# connector.net
KiCad netlist of a schematic drawn in Altium Designer
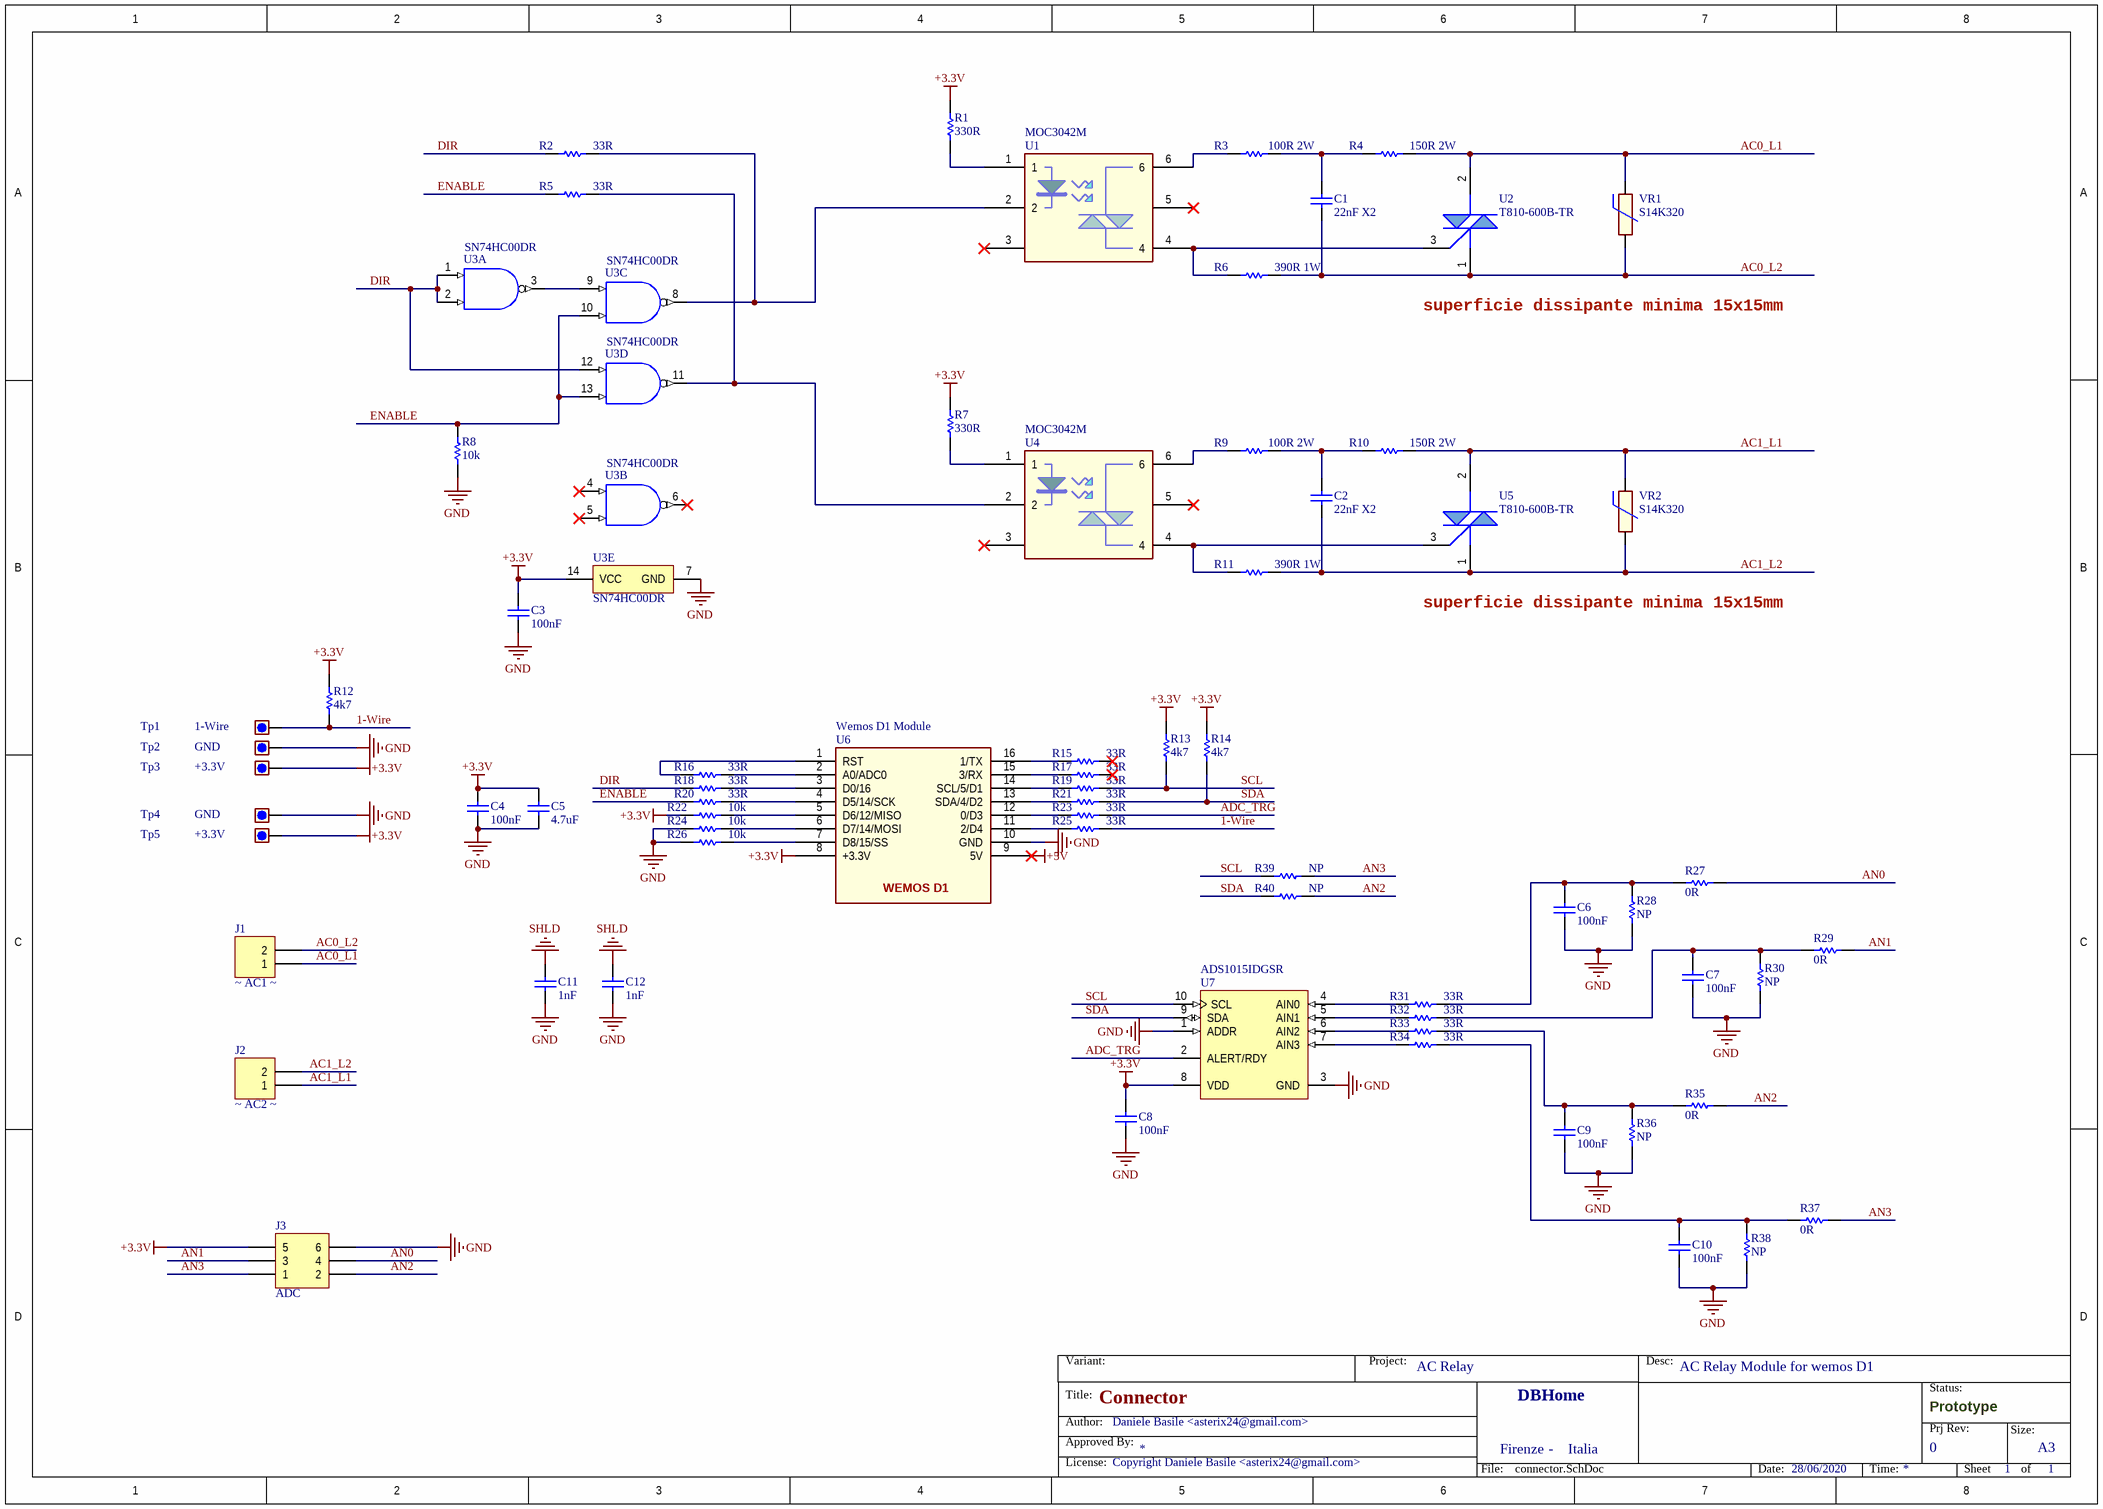
[diagram p0: connector.SchDoc]

(export (version "E")
  (design (tool "Eeschema 10.0.6"))
  (components
    (comp (ref "C1")
      (value "22nF X2")
      (footprint "RADIAL-10MM")
      (description "Capacitor X2 275V")
      (libsource (lib "develer_library") (part "Cap"))
    )
    (comp (ref "C2")
      (value "22nF X2")
      (footprint "RADIAL-10MM")
      (description "Capacitor X2 275V")
      (libsource (lib "develer_library") (part "Cap"))
    )
    (comp (ref "C3")
      (value "100nF")
      (footprint "0402_[1005]")
      (description "Capacitor")
      (libsource (lib "develer_library") (part "Cap"))
    )
    (comp (ref "C4")
      (value "100nF")
      (footprint "0402_[1005]")
      (description "Capacitor")
      (libsource (lib "develer_library") (part "Cap"))
    )
    (comp (ref "C5")
      (value "4.7uF")
      (footprint "0805_[2012]")
      (description "Capacitor")
      (libsource (lib "develer_library") (part "Cap"))
    )
    (comp (ref "C6")
      (value "100nF")
      (footprint "0402_[1005]")
      (description "Capacitor")
      (libsource (lib "develer_library") (part "Cap"))
    )
    (comp (ref "C7")
      (value "100nF")
      (footprint "0402_[1005]")
      (description "Capacitor")
      (libsource (lib "develer_library") (part "Cap"))
    )
    (comp (ref "C8")
      (value "100nF")
      (footprint "0402_[1005]")
      (description "Capacitor")
      (libsource (lib "develer_library") (part "Cap"))
    )
    (comp (ref "C9")
      (value "100nF")
      (footprint "0402_[1005]")
      (description "Capacitor")
      (libsource (lib "develer_library") (part "Cap"))
    )
    (comp (ref "C10")
      (value "100nF")
      (footprint "0402_[1005]")
      (description "Capacitor")
      (libsource (lib "develer_library") (part "Cap"))
    )
    (comp (ref "C11")
      (value "1nF")
      (footprint "0603_[1608]")
      (description "Capacitor")
      (libsource (lib "develer_library") (part "Cap"))
    )
    (comp (ref "C12")
      (value "1nF")
      (footprint "0603_[1608]")
      (description "Capacitor")
      (libsource (lib "develer_library") (part "Cap"))
    )
    (comp (ref "J1")
      (value "~ AC1 ~")
      (footprint "CON_WIRE_SCREW_2x1_5MM_THD")
      (description "Header, 2-Pin")
      (fields (field (name "PUBLISHER") "Altium Limited"))
      (libsource (lib "Miscellaneous Connectors") (part "Header 2"))
    )
    (comp (ref "J2")
      (value "~ AC2 ~")
      (footprint "CON_WIRE_SCREW_2x1_5MM_THD")
      (description "Header, 2-Pin")
      (fields (field (name "PUBLISHER") "Altium Limited"))
      (libsource (lib "Miscellaneous Connectors") (part "Header 2"))
    )
    (comp (ref "J3")
      (value "ADC")
      (footprint "CON_6P_WAGO_3.5mm")
      (description "Header, 3-Pin, Dual row")
      (fields (field (name "PUBLISHER") "Altium Limited"))
      (libsource (lib "Miscellaneous Connectors") (part "Header 3X2"))
    )
    (comp (ref "R1")
      (value "330R")
      (footprint "0402_[1005]")
      (description "Resistor")
      (fields (field (name "PUBLISHER") "Develer srl"))
      (libsource (lib "develer_library") (part "Res1"))
    )
    (comp (ref "R2")
      (value "33R")
      (footprint "0402_[1005]")
      (description "Resistor")
      (fields (field (name "PUBLISHER") "Develer srl"))
      (libsource (lib "develer_library") (part "Res1"))
    )
    (comp (ref "R3")
      (value "100R 2W")
      (footprint "2512_[6432]")
      (description "Resistor 300V (Walsin WF25P271)")
      (fields (field (name "PUBLISHER") "Develer srl"))
      (libsource (lib "develer_library") (part "Res1"))
    )
    (comp (ref "R4")
      (value "150R 2W")
      (footprint "2512_[6432]")
      (description "Resistor 2W 300V (Walsin WF25P471)")
      (fields (field (name "PUBLISHER") "Develer srl"))
      (libsource (lib "develer_library") (part "Res1"))
    )
    (comp (ref "R5")
      (value "33R")
      (footprint "0402_[1005]")
      (description "Resistor")
      (fields (field (name "PUBLISHER") "Develer srl"))
      (libsource (lib "develer_library") (part "Res1"))
    )
    (comp (ref "R6")
      (value "390R 1W")
      (footprint "2512_[6432]")
      (description "Resistor 1W 200V")
      (fields (field (name "PUBLISHER") "Develer srl"))
      (libsource (lib "develer_library") (part "Res1"))
    )
    (comp (ref "R7")
      (value "330R")
      (footprint "0402_[1005]")
      (description "Resistor")
      (fields (field (name "PUBLISHER") "Develer srl"))
      (libsource (lib "develer_library") (part "Res1"))
    )
    (comp (ref "R8")
      (value "10k")
      (footprint "0402_[1005]")
      (description "Resistor")
      (fields (field (name "PUBLISHER") "Develer srl"))
      (libsource (lib "develer_library") (part "Res1"))
    )
    (comp (ref "R9")
      (value "100R 2W")
      (footprint "2512_[6432]")
      (description "Resistor 300V (Walsin WF25P271)")
      (fields (field (name "PUBLISHER") "Develer srl"))
      (libsource (lib "develer_library") (part "Res1"))
    )
    (comp (ref "R10")
      (value "150R 2W")
      (footprint "2512_[6432]")
      (description "Resistor 2W 300V (Walsin WF25P471)")
      (fields (field (name "PUBLISHER") "Develer srl"))
      (libsource (lib "develer_library") (part "Res1"))
    )
    (comp (ref "R11")
      (value "390R 1W")
      (footprint "2512_[6432]")
      (description "Resistor 1W 200V")
      (fields (field (name "PUBLISHER") "Develer srl"))
      (libsource (lib "develer_library") (part "Res1"))
    )
    (comp (ref "R12")
      (value "4k7")
      (footprint "0402_[1005]")
      (description "Resistor")
      (fields (field (name "PUBLISHER") "Develer srl"))
      (libsource (lib "develer_library") (part "Res1"))
    )
    (comp (ref "R13")
      (value "4k7")
      (footprint "0402_[1005]")
      (description "Resistor")
      (fields (field (name "PUBLISHER") "Develer srl"))
      (libsource (lib "develer_library") (part "Res1"))
    )
    (comp (ref "R14")
      (value "4k7")
      (footprint "0402_[1005]")
      (description "Resistor")
      (fields (field (name "PUBLISHER") "Develer srl"))
      (libsource (lib "develer_library") (part "Res1"))
    )
    (comp (ref "R15")
      (value "33R")
      (footprint "0402_[1005]")
      (description "Resistor")
      (fields (field (name "PUBLISHER") "Develer srl"))
      (libsource (lib "develer_library") (part "Res1"))
    )
    (comp (ref "R16")
      (value "33R")
      (footprint "0402_[1005]")
      (description "Resistor")
      (fields (field (name "PUBLISHER") "Develer srl"))
      (libsource (lib "develer_library") (part "Res1"))
    )
    (comp (ref "R17")
      (value "33R")
      (footprint "0402_[1005]")
      (description "Resistor")
      (fields (field (name "PUBLISHER") "Develer srl"))
      (libsource (lib "develer_library") (part "Res1"))
    )
    (comp (ref "R18")
      (value "33R")
      (footprint "0402_[1005]")
      (description "Resistor")
      (fields (field (name "PUBLISHER") "Develer srl"))
      (libsource (lib "develer_library") (part "Res1"))
    )
    (comp (ref "R19")
      (value "33R")
      (footprint "0402_[1005]")
      (description "Resistor")
      (fields (field (name "PUBLISHER") "Develer srl"))
      (libsource (lib "develer_library") (part "Res1"))
    )
    (comp (ref "R20")
      (value "33R")
      (footprint "0402_[1005]")
      (description "Resistor")
      (fields (field (name "PUBLISHER") "Develer srl"))
      (libsource (lib "develer_library") (part "Res1"))
    )
    (comp (ref "R21")
      (value "33R")
      (footprint "0402_[1005]")
      (description "Resistor")
      (fields (field (name "PUBLISHER") "Develer srl"))
      (libsource (lib "develer_library") (part "Res1"))
    )
    (comp (ref "R22")
      (value "10k")
      (footprint "0402_[1005]")
      (description "Resistor")
      (fields (field (name "PUBLISHER") "Develer srl"))
      (libsource (lib "develer_library") (part "Res1"))
    )
    (comp (ref "R23")
      (value "33R")
      (footprint "0402_[1005]")
      (description "Resistor")
      (fields (field (name "PUBLISHER") "Develer srl"))
      (libsource (lib "develer_library") (part "Res1"))
    )
    (comp (ref "R24")
      (value "10k")
      (footprint "0402_[1005]")
      (description "Resistor")
      (fields (field (name "PUBLISHER") "Develer srl"))
      (libsource (lib "develer_library") (part "Res1"))
    )
    (comp (ref "R25")
      (value "33R")
      (footprint "0402_[1005]")
      (description "Resistor")
      (fields (field (name "PUBLISHER") "Develer srl"))
      (libsource (lib "develer_library") (part "Res1"))
    )
    (comp (ref "R26")
      (value "10k")
      (footprint "0402_[1005]")
      (description "Resistor")
      (fields (field (name "PUBLISHER") "Develer srl"))
      (libsource (lib "develer_library") (part "Res1"))
    )
    (comp (ref "R27")
      (value "0R")
      (footprint "0402_[1005]")
      (description "Resistor")
      (fields (field (name "PUBLISHER") "Develer srl"))
      (libsource (lib "develer_library") (part "Res1"))
    )
    (comp (ref "R28")
      (value "NP")
      (footprint "0402_[1005]")
      (description "Resistor")
      (fields (field (name "PUBLISHER") "Develer srl"))
      (libsource (lib "develer_library") (part "Res1"))
    )
    (comp (ref "R29")
      (value "0R")
      (footprint "0402_[1005]")
      (description "Resistor")
      (fields (field (name "PUBLISHER") "Develer srl"))
      (libsource (lib "develer_library") (part "Res1"))
    )
    (comp (ref "R30")
      (value "NP")
      (footprint "0402_[1005]")
      (description "Resistor")
      (fields (field (name "PUBLISHER") "Develer srl"))
      (libsource (lib "develer_library") (part "Res1"))
    )
    (comp (ref "R31")
      (value "33R")
      (footprint "0402_[1005]")
      (description "Resistor")
      (fields (field (name "PUBLISHER") "Develer srl"))
      (libsource (lib "develer_library") (part "Res1"))
    )
    (comp (ref "R32")
      (value "33R")
      (footprint "0402_[1005]")
      (description "Resistor")
      (fields (field (name "PUBLISHER") "Develer srl"))
      (libsource (lib "develer_library") (part "Res1"))
    )
    (comp (ref "R33")
      (value "33R")
      (footprint "0402_[1005]")
      (description "Resistor")
      (fields (field (name "PUBLISHER") "Develer srl"))
      (libsource (lib "develer_library") (part "Res1"))
    )
    (comp (ref "R34")
      (value "33R")
      (footprint "0402_[1005]")
      (description "Resistor")
      (fields (field (name "PUBLISHER") "Develer srl"))
      (libsource (lib "develer_library") (part "Res1"))
    )
    (comp (ref "R35")
      (value "0R")
      (footprint "0402_[1005]")
      (description "Resistor")
      (fields (field (name "PUBLISHER") "Develer srl"))
      (libsource (lib "develer_library") (part "Res1"))
    )
    (comp (ref "R36")
      (value "NP")
      (footprint "0402_[1005]")
      (description "Resistor")
      (fields (field (name "PUBLISHER") "Develer srl"))
      (libsource (lib "develer_library") (part "Res1"))
    )
    (comp (ref "R37")
      (value "0R")
      (footprint "0402_[1005]")
      (description "Resistor")
      (fields (field (name "PUBLISHER") "Develer srl"))
      (libsource (lib "develer_library") (part "Res1"))
    )
    (comp (ref "R38")
      (value "NP")
      (footprint "0402_[1005]")
      (description "Resistor")
      (fields (field (name "PUBLISHER") "Develer srl"))
      (libsource (lib "develer_library") (part "Res1"))
    )
    (comp (ref "R39")
      (value "NP")
      (footprint "0402_[1005]")
      (description "Resistor")
      (fields (field (name "PUBLISHER") "Develer srl"))
      (libsource (lib "develer_library") (part "Res1"))
    )
    (comp (ref "R40")
      (value "NP")
      (footprint "0402_[1005]")
      (description "Resistor")
      (fields (field (name "PUBLISHER") "Develer srl"))
      (libsource (lib "develer_library") (part "Res1"))
    )
    (comp (ref "Tp1")
      (value "1-Wire")
      (footprint "TEST_POINT_SMD_R5x3MM")
      (libsource (lib "develer_library") (part "Test_point"))
    )
    (comp (ref "Tp2")
      (value "GND")
      (footprint "TEST_POINT_SMD_R5x3MM")
      (libsource (lib "develer_library") (part "Test_point"))
    )
    (comp (ref "Tp3")
      (value "+3.3V")
      (footprint "TEST_POINT_SMD_R5x3MM")
      (libsource (lib "develer_library") (part "Test_point"))
    )
    (comp (ref "Tp4")
      (value "GND")
      (footprint "TEST_POINT_SMD_R5x3MM")
      (libsource (lib "develer_library") (part "Test_point"))
    )
    (comp (ref "Tp5")
      (value "+3.3V")
      (footprint "TEST_POINT_SMD_R5x3MM")
      (libsource (lib "develer_library") (part "Test_point"))
    )
    (comp (ref "U1")
      (value "MOC3042M")
      (footprint "SOIC6_OPTO")
      (description "Opto-triac")
      (fields (field (name "PUBLISHER") "Develer srl"))
      (libsource (lib "develer_library") (part "MOC302xS"))
    )
    (comp (ref "U2")
      (value "T810-600B-TR")
      (footprint "TO-252_D2PAK_LARGEPAD")
      (description "triac")
      (fields (field (name "PUBLISHER") "Develer srl"))
      (libsource (lib "develer_library") (part "triac"))
    )
    (comp (ref "U3")
      (value "SN74HC00DR")
      (footprint "SOIC14")
      (description "Quad 2-Input Positive-NAND Gates, D0014A, LARGE T&R")
      (fields
        (field (name "GENERIC PART NUMBER") "SN74HC00")
        (field (name "MANUFACTURER") "Texas Instruments")
      )
      (libsource (lib "develer_library") (part "TI-NAND-4-2IN-14_G"))
    )
    (comp (ref "U4")
      (value "MOC3042M")
      (footprint "SOIC6_OPTO")
      (description "Opto-triac")
      (fields (field (name "PUBLISHER") "Develer srl"))
      (libsource (lib "develer_library") (part "MOC302xS"))
    )
    (comp (ref "U5")
      (value "T810-600B-TR")
      (footprint "TO-252_D2PAK_LARGEPAD")
      (description "triac")
      (fields (field (name "PUBLISHER") "Develer srl"))
      (libsource (lib "develer_library") (part "triac"))
    )
    (comp (ref "U6")
      (value "Wemos D1 Module")
      (footprint "WEMOS_D1")
      (description "ComponetDescritions (altrenative1; alternativ2)")
      (fields (field (name "PUBLISHER") "Develer srl"))
      (libsource (lib "develer_library") (part "WEMOS D1"))
    )
    (comp (ref "U7")
      (value "ADS1015IDGSR")
      (footprint "MSOP50P490X110-10P")
      (fields (field (name "MANUFACTURER") "Texas Instruments"))
      (libsource (lib "develer_library") (part "TI-ADS1015_1115-10"))
    )
    (comp (ref "VR1")
      (value "S14K320")
      (footprint "VAR_DISC_7.5MM_THD")
      (description "ComponetDescritions (altrenative1; alternativ2)")
      (fields (field (name "PUBLISHER") "Develer srl"))
      (libsource (lib "develer_library") (part "VARISTOR"))
    )
    (comp (ref "VR2")
      (value "S14K320")
      (footprint "VAR_DISC_7.5MM_THD")
      (description "ComponetDescritions (altrenative1; alternativ2)")
      (fields (field (name "PUBLISHER") "Develer srl"))
      (libsource (lib "develer_library") (part "VARISTOR"))
    )
  )
  (nets
    (net (code "1") (name "+3.3V") (class "Default")
      (node (ref "C3") (pin "2") (pinfunction "2_2") (pintype "passive"))
      (node (ref "C4") (pin "2") (pinfunction "2_2") (pintype "passive"))
      (node (ref "C5") (pin "2") (pinfunction "2_2") (pintype "passive"))
      (node (ref "C8") (pin "2") (pinfunction "2_2") (pintype "passive"))
      (node (ref "J3") (pin "5") (pinfunction "5_5") (pintype "passive"))
      (node (ref "R1") (pin "2") (pinfunction "2_2") (pintype "passive"))
      (node (ref "R12") (pin "2") (pinfunction "2_2") (pintype "passive"))
      (node (ref "R13") (pin "2") (pinfunction "2_2") (pintype "passive"))
      (node (ref "R14") (pin "2") (pinfunction "2_2") (pintype "passive"))
      (node (ref "R22") (pin "2") (pinfunction "2_2") (pintype "passive"))
      (node (ref "R7") (pin "2") (pinfunction "2_2") (pintype "passive"))
      (node (ref "Tp3") (pin "1") (pinfunction "1_1") (pintype "passive"))
      (node (ref "Tp5") (pin "1") (pinfunction "1_1") (pintype "passive"))
      (node (ref "U3") (pin "14") (pinfunction "VCC_14") (pintype "power_in"))
      (node (ref "U6") (pin "8") (pinfunction "+3.3V_8") (pintype "passive"))
      (node (ref "U7") (pin "8") (pinfunction "VDD_8") (pintype "power_in"))
    )
    (net (code "2") (name "+5V") (class "Default")
      (node (ref "U6") (pin "9") (pinfunction "5V_9") (pintype "passive"))
    )
    (net (code "3") (name "/1-Wire") (class "Default")
      (node (ref "R12") (pin "1") (pinfunction "1_1") (pintype "passive"))
      (node (ref "R25") (pin "1") (pinfunction "1_1") (pintype "passive"))
      (node (ref "Tp1") (pin "1") (pinfunction "1_1") (pintype "passive"))
    )
    (net (code "4") (name "/AC0_L1") (class "Default")
      (node (ref "J1") (pin "1") (pinfunction "1_1") (pintype "passive"))
      (node (ref "R4") (pin "1") (pinfunction "1_1") (pintype "passive"))
      (node (ref "U2") (pin "2") (pinfunction "2_2") (pintype "passive"))
      (node (ref "VR1") (pin "2") (pinfunction "2_2") (pintype "passive"))
    )
    (net (code "5") (name "/AC0_L2") (class "Default")
      (node (ref "C1") (pin "1") (pinfunction "1_1") (pintype "passive"))
      (node (ref "J1") (pin "2") (pinfunction "2_2") (pintype "passive"))
      (node (ref "R6") (pin "1") (pinfunction "1_1") (pintype "passive"))
      (node (ref "U2") (pin "1") (pinfunction "1_1") (pintype "passive"))
      (node (ref "VR1") (pin "1") (pinfunction "1_1") (pintype "passive"))
    )
    (net (code "6") (name "/AC1_L1") (class "Default")
      (node (ref "J2") (pin "1") (pinfunction "1_1") (pintype "passive"))
      (node (ref "R10") (pin "1") (pinfunction "1_1") (pintype "passive"))
      (node (ref "U5") (pin "2") (pinfunction "2_2") (pintype "passive"))
      (node (ref "VR2") (pin "2") (pinfunction "2_2") (pintype "passive"))
    )
    (net (code "7") (name "/AC1_L2") (class "Default")
      (node (ref "C2") (pin "1") (pinfunction "1_1") (pintype "passive"))
      (node (ref "J2") (pin "2") (pinfunction "2_2") (pintype "passive"))
      (node (ref "R11") (pin "1") (pinfunction "1_1") (pintype "passive"))
      (node (ref "U5") (pin "1") (pinfunction "1_1") (pintype "passive"))
      (node (ref "VR2") (pin "1") (pinfunction "1_1") (pintype "passive"))
    )
    (net (code "8") (name "/ADC_TRG") (class "Default")
      (node (ref "R23") (pin "1") (pinfunction "1_1") (pintype "passive"))
      (node (ref "U7") (pin "2") (pinfunction "ALERT/RDY_2") (pintype "open_collector"))
    )
    (net (code "9") (name "/AN0") (class "Default")
      (node (ref "J3") (pin "4") (pinfunction "4_4") (pintype "passive"))
      (node (ref "R27") (pin "2") (pinfunction "2_2") (pintype "passive"))
    )
    (net (code "10") (name "/AN1") (class "Default")
      (node (ref "J3") (pin "3") (pinfunction "3_3") (pintype "passive"))
      (node (ref "R29") (pin "2") (pinfunction "2_2") (pintype "passive"))
    )
    (net (code "11") (name "/AN2") (class "Default")
      (node (ref "J3") (pin "2") (pinfunction "2_2") (pintype "passive"))
      (node (ref "R35") (pin "2") (pinfunction "2_2") (pintype "passive"))
      (node (ref "R40") (pin "2") (pinfunction "2_2") (pintype "passive"))
    )
    (net (code "12") (name "/AN3") (class "Default")
      (node (ref "J3") (pin "1") (pinfunction "1_1") (pintype "passive"))
      (node (ref "R37") (pin "2") (pinfunction "2_2") (pintype "passive"))
      (node (ref "R39") (pin "2") (pinfunction "2_2") (pintype "passive"))
    )
    (net (code "13") (name "/DIR") (class "Default")
      (node (ref "R18") (pin "2") (pinfunction "2_2") (pintype "passive"))
      (node (ref "R2") (pin "2") (pinfunction "2_2") (pintype "passive"))
      (node (ref "U3") (pin "1") (pinfunction "1A_1") (pintype "input"))
      (node (ref "U3") (pin "12") (pinfunction "4A_12") (pintype "input"))
      (node (ref "U3") (pin "2") (pinfunction "1B_2") (pintype "input"))
    )
    (net (code "14") (name "/ENABLE") (class "Default")
      (node (ref "R20") (pin "2") (pinfunction "2_2") (pintype "passive"))
      (node (ref "R5") (pin "2") (pinfunction "2_2") (pintype "passive"))
      (node (ref "R8") (pin "1") (pinfunction "1_1") (pintype "passive"))
      (node (ref "U3") (pin "10") (pinfunction "3B_10") (pintype "input"))
      (node (ref "U3") (pin "13") (pinfunction "4B_13") (pintype "input"))
    )
    (net (code "15") (name "/SCL") (class "Default")
      (node (ref "R13") (pin "1") (pinfunction "1_1") (pintype "passive"))
      (node (ref "R19") (pin "1") (pinfunction "1_1") (pintype "passive"))
      (node (ref "R39") (pin "1") (pinfunction "1_1") (pintype "passive"))
      (node (ref "U7") (pin "10") (pinfunction "SCL_10") (pintype "input"))
    )
    (net (code "16") (name "/SDA") (class "Default")
      (node (ref "R14") (pin "1") (pinfunction "1_1") (pintype "passive"))
      (node (ref "R21") (pin "1") (pinfunction "1_1") (pintype "passive"))
      (node (ref "R40") (pin "1") (pinfunction "1_1") (pintype "passive"))
      (node (ref "U7") (pin "9") (pinfunction "SDA_9") (pintype "bidirectional"))
    )
    (net (code "17") (name "GND") (class "Default")
      (node (ref "C10") (pin "1") (pinfunction "1_1") (pintype "passive"))
      (node (ref "C11") (pin "1") (pinfunction "1_1") (pintype "passive"))
      (node (ref "C12") (pin "1") (pinfunction "1_1") (pintype "passive"))
      (node (ref "C3") (pin "1") (pinfunction "1_1") (pintype "passive"))
      (node (ref "C4") (pin "1") (pinfunction "1_1") (pintype "passive"))
      (node (ref "C5") (pin "1") (pinfunction "1_1") (pintype "passive"))
      (node (ref "C6") (pin "1") (pinfunction "1_1") (pintype "passive"))
      (node (ref "C7") (pin "1") (pinfunction "1_1") (pintype "passive"))
      (node (ref "C8") (pin "1") (pinfunction "1_1") (pintype "passive"))
      (node (ref "C9") (pin "1") (pinfunction "1_1") (pintype "passive"))
      (node (ref "J3") (pin "6") (pinfunction "6_6") (pintype "passive"))
      (node (ref "R24") (pin "2") (pinfunction "2_2") (pintype "passive"))
      (node (ref "R26") (pin "2") (pinfunction "2_2") (pintype "passive"))
      (node (ref "R28") (pin "2") (pinfunction "2_2") (pintype "passive"))
      (node (ref "R30") (pin "2") (pinfunction "2_2") (pintype "passive"))
      (node (ref "R36") (pin "2") (pinfunction "2_2") (pintype "passive"))
      (node (ref "R38") (pin "2") (pinfunction "2_2") (pintype "passive"))
      (node (ref "R8") (pin "2") (pinfunction "2_2") (pintype "passive"))
      (node (ref "Tp2") (pin "1") (pinfunction "1_1") (pintype "passive"))
      (node (ref "Tp4") (pin "1") (pinfunction "1_1") (pintype "passive"))
      (node (ref "U3") (pin "7") (pinfunction "GND_7") (pintype "power_in"))
      (node (ref "U6") (pin "10") (pinfunction "GND_10") (pintype "passive"))
      (node (ref "U7") (pin "1") (pinfunction "ADDR_1") (pintype "input"))
      (node (ref "U7") (pin "3") (pinfunction "GND_3") (pintype "power_in"))
    )
    (net (code "18") (name "Net-(C1-Pad2)") (class "Default")
      (node (ref "C1") (pin "2") (pinfunction "2_2") (pintype "passive"))
      (node (ref "R3") (pin "1") (pinfunction "1_1") (pintype "passive"))
      (node (ref "R4") (pin "2") (pinfunction "2_2") (pintype "passive"))
    )
    (net (code "19") (name "Net-(C2-Pad2)") (class "Default")
      (node (ref "C2") (pin "2") (pinfunction "2_2") (pintype "passive"))
      (node (ref "R10") (pin "2") (pinfunction "2_2") (pintype "passive"))
      (node (ref "R9") (pin "1") (pinfunction "1_1") (pintype "passive"))
    )
    (net (code "20") (name "Net-(C6-Pad2)") (class "Default")
      (node (ref "C6") (pin "2") (pinfunction "2_2") (pintype "passive"))
      (node (ref "R27") (pin "1") (pinfunction "1_1") (pintype "passive"))
      (node (ref "R28") (pin "1") (pinfunction "1_1") (pintype "passive"))
      (node (ref "R31") (pin "1") (pinfunction "1_1") (pintype "passive"))
    )
    (net (code "21") (name "Net-(C7-Pad2)") (class "Default")
      (node (ref "C7") (pin "2") (pinfunction "2_2") (pintype "passive"))
      (node (ref "R29") (pin "1") (pinfunction "1_1") (pintype "passive"))
      (node (ref "R30") (pin "1") (pinfunction "1_1") (pintype "passive"))
      (node (ref "R32") (pin "1") (pinfunction "1_1") (pintype "passive"))
    )
    (net (code "22") (name "Net-(C9-Pad2)") (class "Default")
      (node (ref "C9") (pin "2") (pinfunction "2_2") (pintype "passive"))
      (node (ref "R33") (pin "1") (pinfunction "1_1") (pintype "passive"))
      (node (ref "R35") (pin "1") (pinfunction "1_1") (pintype "passive"))
      (node (ref "R36") (pin "1") (pinfunction "1_1") (pintype "passive"))
    )
    (net (code "23") (name "Net-(C10-Pad2)") (class "Default")
      (node (ref "C10") (pin "2") (pinfunction "2_2") (pintype "passive"))
      (node (ref "R34") (pin "1") (pinfunction "1_1") (pintype "passive"))
      (node (ref "R37") (pin "1") (pinfunction "1_1") (pintype "passive"))
      (node (ref "R38") (pin "1") (pinfunction "1_1") (pintype "passive"))
    )
    (net (code "24") (name "Net-(R1-Pad1)") (class "Default")
      (node (ref "R1") (pin "1") (pinfunction "1_1") (pintype "passive"))
      (node (ref "U1") (pin "1") (pinfunction "1_1") (pintype "passive"))
    )
    (net (code "25") (name "Net-(R3-Pad2)") (class "Default")
      (node (ref "R3") (pin "2") (pinfunction "2_2") (pintype "passive"))
      (node (ref "U1") (pin "6") (pinfunction "6_6") (pintype "passive"))
    )
    (net (code "26") (name "Net-(R6-Pad2)") (class "Default")
      (node (ref "R6") (pin "2") (pinfunction "2_2") (pintype "passive"))
      (node (ref "U1") (pin "4") (pinfunction "4_4") (pintype "passive"))
      (node (ref "U2") (pin "3") (pinfunction "3_3") (pintype "passive"))
    )
    (net (code "27") (name "Net-(R7-Pad1)") (class "Default")
      (node (ref "R7") (pin "1") (pinfunction "1_1") (pintype "passive"))
      (node (ref "U4") (pin "1") (pinfunction "1_1") (pintype "passive"))
    )
    (net (code "28") (name "Net-(R9-Pad2)") (class "Default")
      (node (ref "R9") (pin "2") (pinfunction "2_2") (pintype "passive"))
      (node (ref "U4") (pin "6") (pinfunction "6_6") (pintype "passive"))
    )
    (net (code "29") (name "Net-(R11-Pad2)") (class "Default")
      (node (ref "R11") (pin "2") (pinfunction "2_2") (pintype "passive"))
      (node (ref "U4") (pin "4") (pinfunction "4_4") (pintype "passive"))
      (node (ref "U5") (pin "3") (pinfunction "3_3") (pintype "passive"))
    )
    (net (code "30") (name "Net-(U3A-1Y)") (class "Default")
      (node (ref "U3") (pin "3") (pinfunction "1Y_3") (pintype "output"))
      (node (ref "U3") (pin "9") (pinfunction "3A_9") (pintype "input"))
    )
    (net (code "31") (name "Net-(U3C-3Y)") (class "Default")
      (node (ref "R2") (pin "1") (pinfunction "1_1") (pintype "passive"))
      (node (ref "U1") (pin "2") (pinfunction "2_2") (pintype "passive"))
      (node (ref "U3") (pin "8") (pinfunction "3Y_8") (pintype "output"))
    )
    (net (code "32") (name "Net-(U3D-4Y)") (class "Default")
      (node (ref "R5") (pin "1") (pinfunction "1_1") (pintype "passive"))
      (node (ref "U3") (pin "11") (pinfunction "4Y_11") (pintype "output"))
      (node (ref "U4") (pin "2") (pinfunction "2_2") (pintype "passive"))
    )
    (net (code "33") (name "Net-(U6-0{slash}D3)") (class "Default")
      (node (ref "R23") (pin "2") (pinfunction "2_2") (pintype "passive"))
      (node (ref "U6") (pin "12") (pinfunction "0/D3_12") (pintype "passive"))
    )
    (net (code "34") (name "Net-(U6-1{slash}TX)") (class "Default")
      (node (ref "R15") (pin "2") (pinfunction "2_2") (pintype "passive"))
      (node (ref "U6") (pin "16") (pinfunction "1/TX_16") (pintype "passive"))
    )
    (net (code "35") (name "Net-(U6-2{slash}D4)") (class "Default")
      (node (ref "R25") (pin "2") (pinfunction "2_2") (pintype "passive"))
      (node (ref "U6") (pin "11") (pinfunction "2/D4_11") (pintype "passive"))
    )
    (net (code "36") (name "Net-(U6-3{slash}RX)") (class "Default")
      (node (ref "R17") (pin "2") (pinfunction "2_2") (pintype "passive"))
      (node (ref "U6") (pin "15") (pinfunction "3/RX_15") (pintype "passive"))
    )
    (net (code "37") (name "Net-(U6-A0{slash}ADC0)") (class "Default")
      (node (ref "R16") (pin "1") (pinfunction "1_1") (pintype "passive"))
      (node (ref "U6") (pin "2") (pinfunction "A0/ADC0_2") (pintype "passive"))
    )
    (net (code "38") (name "Net-(U6-D0{slash}16)") (class "Default")
      (node (ref "R18") (pin "1") (pinfunction "1_1") (pintype "passive"))
      (node (ref "U6") (pin "3") (pinfunction "D0/16_3") (pintype "passive"))
    )
    (net (code "39") (name "Net-(U6-D5{slash}14{slash}SCK)") (class "Default")
      (node (ref "R20") (pin "1") (pinfunction "1_1") (pintype "passive"))
      (node (ref "U6") (pin "4") (pinfunction "D5/14/SCK_4") (pintype "passive"))
    )
    (net (code "40") (name "Net-(U6-D6{slash}12{slash}MISO)") (class "Default")
      (node (ref "R22") (pin "1") (pinfunction "1_1") (pintype "passive"))
      (node (ref "U6") (pin "5") (pinfunction "D6/12/MISO_5") (pintype "passive"))
    )
    (net (code "41") (name "Net-(U6-D7{slash}14{slash}MOSI)") (class "Default")
      (node (ref "R24") (pin "1") (pinfunction "1_1") (pintype "passive"))
      (node (ref "U6") (pin "6") (pinfunction "D7/14/MOSI_6") (pintype "passive"))
    )
    (net (code "42") (name "Net-(U6-D8{slash}15{slash}SS)") (class "Default")
      (node (ref "R26") (pin "1") (pinfunction "1_1") (pintype "passive"))
      (node (ref "U6") (pin "7") (pinfunction "D8/15/SS_7") (pintype "passive"))
    )
    (net (code "43") (name "Net-(U6-RST)") (class "Default")
      (node (ref "R16") (pin "2") (pinfunction "2_2") (pintype "passive"))
      (node (ref "U6") (pin "1") (pinfunction "RST_1") (pintype "passive"))
    )
    (net (code "44") (name "Net-(U6-SCL{slash}5{slash}D1)") (class "Default")
      (node (ref "R19") (pin "2") (pinfunction "2_2") (pintype "passive"))
      (node (ref "U6") (pin "14") (pinfunction "SCL/5/D1_14") (pintype "passive"))
    )
    (net (code "45") (name "Net-(U6-SDA{slash}4{slash}D2)") (class "Default")
      (node (ref "R21") (pin "2") (pinfunction "2_2") (pintype "passive"))
      (node (ref "U6") (pin "13") (pinfunction "SDA/4/D2_13") (pintype "passive"))
    )
    (net (code "46") (name "Net-(U7-AIN0)") (class "Default")
      (node (ref "R31") (pin "2") (pinfunction "2_2") (pintype "passive"))
      (node (ref "U7") (pin "4") (pinfunction "AIN0_4") (pintype "input"))
    )
    (net (code "47") (name "Net-(U7-AIN1)") (class "Default")
      (node (ref "R32") (pin "2") (pinfunction "2_2") (pintype "passive"))
      (node (ref "U7") (pin "5") (pinfunction "AIN1_5") (pintype "input"))
    )
    (net (code "48") (name "Net-(U7-AIN2)") (class "Default")
      (node (ref "R33") (pin "2") (pinfunction "2_2") (pintype "passive"))
      (node (ref "U7") (pin "6") (pinfunction "AIN2_6") (pintype "input"))
    )
    (net (code "49") (name "Net-(U7-AIN3)") (class "Default")
      (node (ref "R34") (pin "2") (pinfunction "2_2") (pintype "passive"))
      (node (ref "U7") (pin "7") (pinfunction "AIN3_7") (pintype "input"))
    )
    (net (code "50") (name "SHLD") (class "Default")
      (node (ref "C11") (pin "2") (pinfunction "2_2") (pintype "passive"))
      (node (ref "C12") (pin "2") (pinfunction "2_2") (pintype "passive"))
    )
    (net (code "51") (name "unconnected-(R15-Pad1)") (class "Default")
      (node (ref "R15") (pin "1") (pinfunction "1_1") (pintype "passive+no_connect"))
    )
    (net (code "52") (name "unconnected-(R17-Pad1)") (class "Default")
      (node (ref "R17") (pin "1") (pinfunction "1_1") (pintype "passive+no_connect"))
    )
    (net (code "53") (name "unconnected-(U1-Pad3)") (class "Default")
      (node (ref "U1") (pin "3") (pinfunction "3_3") (pintype "passive+no_connect"))
    )
    (net (code "54") (name "unconnected-(U1-Pad5)") (class "Default")
      (node (ref "U1") (pin "5") (pinfunction "5_5") (pintype "passive+no_connect"))
    )
    (net (code "55") (name "unconnected-(U3B-2A-Pad4)") (class "Default")
      (node (ref "U3") (pin "4") (pinfunction "2A_4") (pintype "input+no_connect"))
    )
    (net (code "56") (name "unconnected-(U3B-2B-Pad5)") (class "Default")
      (node (ref "U3") (pin "5") (pinfunction "2B_5") (pintype "input+no_connect"))
    )
    (net (code "57") (name "unconnected-(U3B-2Y-Pad6)") (class "Default")
      (node (ref "U3") (pin "6") (pinfunction "2Y_6") (pintype "output+no_connect"))
    )
    (net (code "58") (name "unconnected-(U4-Pad3)") (class "Default")
      (node (ref "U4") (pin "3") (pinfunction "3_3") (pintype "passive+no_connect"))
    )
    (net (code "59") (name "unconnected-(U4-Pad5)") (class "Default")
      (node (ref "U4") (pin "5") (pinfunction "5_5") (pintype "passive+no_connect"))
    )
  )
)
